# PowerConnectors.net
KiCad netlist of a schematic drawn in Altium Designer
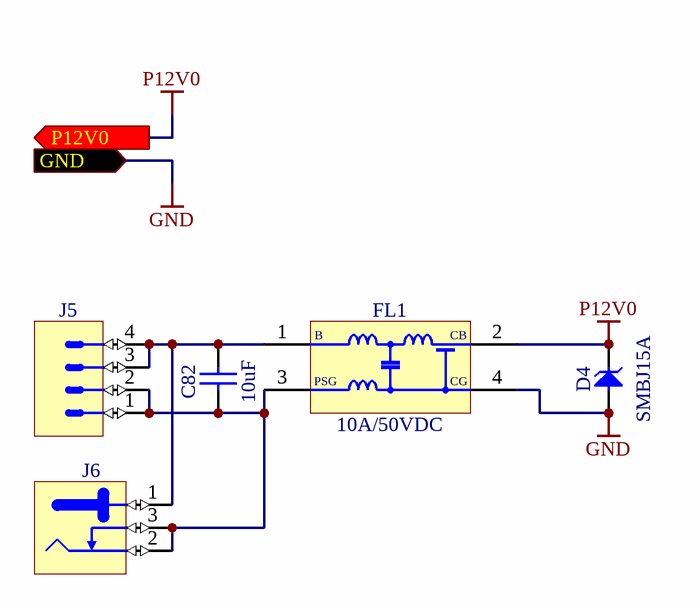
[diagram p0: PowerConnectors.SchDoc]

(export (version "E")
  (design (tool "Eeschema 10.0.6"))
  (components
    (comp (ref "C82")
      (value "10uF")
      (footprint "CAPC3216X190N")
      (description "Non-polarised capacitor")
      (fields
        (field (name "PART NUMBER") "CC1206_10UF_35V_10%_X7R_YUDEN_GMJ316BB7106KLHT")
        (field (name "VOLTAGE") "35V")
        (field (name "AUTHOR") "CERN DEM BC")
      )
      (libsource (lib "Capacitors") (part "Capacitor - non polarized"))
    )
    (comp (ref "D4")
      (value "SMBJ15A")
      (footprint "DIOM5336X265N")
      (description "Zener Diode")
      (fields
        (field (name "VOLTAGE") "15V")
        (field (name "POWER") "600W")
        (field (name "AUTHOR") "CERN DEM JLC")
      )
      (libsource (lib "ICs And Semiconductors") (part "Diode Zener"))
    )
    (comp (ref "FL1")
      (value "10A/50VDC")
      (footprint "FIL_MURATA_BNX02")
      (description "Block Type EMIFIL (LC Combined)")
      (fields
        (field (name "PART NUMBER") "FIL_MURATA_BNX022-01L")
        (field (name "MANUFACTURER") "MURATA")
        (field (name "AUTHOR") "CERN DEM JLC")
      )
      (libsource (lib "Inductors & Transformers") (part "FIL_MURATA_BNX02"))
    )
    (comp (ref "J5")
      (value "~")
      (footprint "MOLEX_39-30-0040")
      (description "Connector 4 Male")
      (fields
        (field (name "PART NUMBER") "MOLEX_39-30-0040")
        (field (name "MANUFACTURER") "MOLEX")
        (field (name "AUTHOR") "CERN DEM JLC")
      )
      (libsource (lib "Connectors") (part "Connector 4 Male"))
    )
    (comp (ref "J6")
      (value "~")
      (footprint "SWITCHCRAFT_712RA")
      (description "2.5 mm Center Pin, 5A, 48V, Right Angle, Through Hole, , DC Power Jack Connector")
      (fields
        (field (name "PART NUMBER") "SWITCHCRAFT_712RA")
        (field (name "MANUFACTURER") "SWITCHCRAFT")
        (field (name "AUTHOR") "CERN DEM JLC")
      )
      (libsource (lib "Connectors") (part "SWITCHCRAFT_712RA"))
    )
  )
  (nets
    (net (code "1") (name "GND") (class "Default")
      (node (ref "D4") (pin "2") (pinfunction "A_2") (pintype "passive"))
      (node (ref "FL1") (pin "4") (pinfunction "CG_4") (pintype "passive"))
    )
    (net (code "2") (name "Net-(FL1-B)") (class "Default")
      (node (ref "C82") (pin "2") (pinfunction "2_2") (pintype "passive"))
      (node (ref "FL1") (pin "1") (pinfunction "B_1") (pintype "passive"))
      (node (ref "J5") (pin "3") (pinfunction "3_3") (pintype "bidirectional"))
      (node (ref "J5") (pin "4") (pinfunction "4_4") (pintype "bidirectional"))
      (node (ref "J6") (pin "1") (pinfunction "1_1") (pintype "bidirectional"))
    )
    (net (code "3") (name "Net-(FL1-PSG)") (class "Default")
      (node (ref "C82") (pin "1") (pinfunction "1_1") (pintype "passive"))
      (node (ref "FL1") (pin "3") (pinfunction "PSG_3") (pintype "passive"))
      (node (ref "J5") (pin "1") (pinfunction "1_1") (pintype "bidirectional"))
      (node (ref "J5") (pin "2") (pinfunction "2_2") (pintype "bidirectional"))
      (node (ref "J6") (pin "2") (pinfunction "2_2") (pintype "bidirectional"))
      (node (ref "J6") (pin "3") (pinfunction "3_3") (pintype "bidirectional"))
    )
    (net (code "4") (name "P12V0") (class "Default")
      (node (ref "D4") (pin "1") (pinfunction "C_1") (pintype "passive"))
      (node (ref "FL1") (pin "2") (pinfunction "CB_2") (pintype "passive"))
    )
  )
)
